# SDCard.net
KiCad netlist of a schematic drawn in Altium Designer
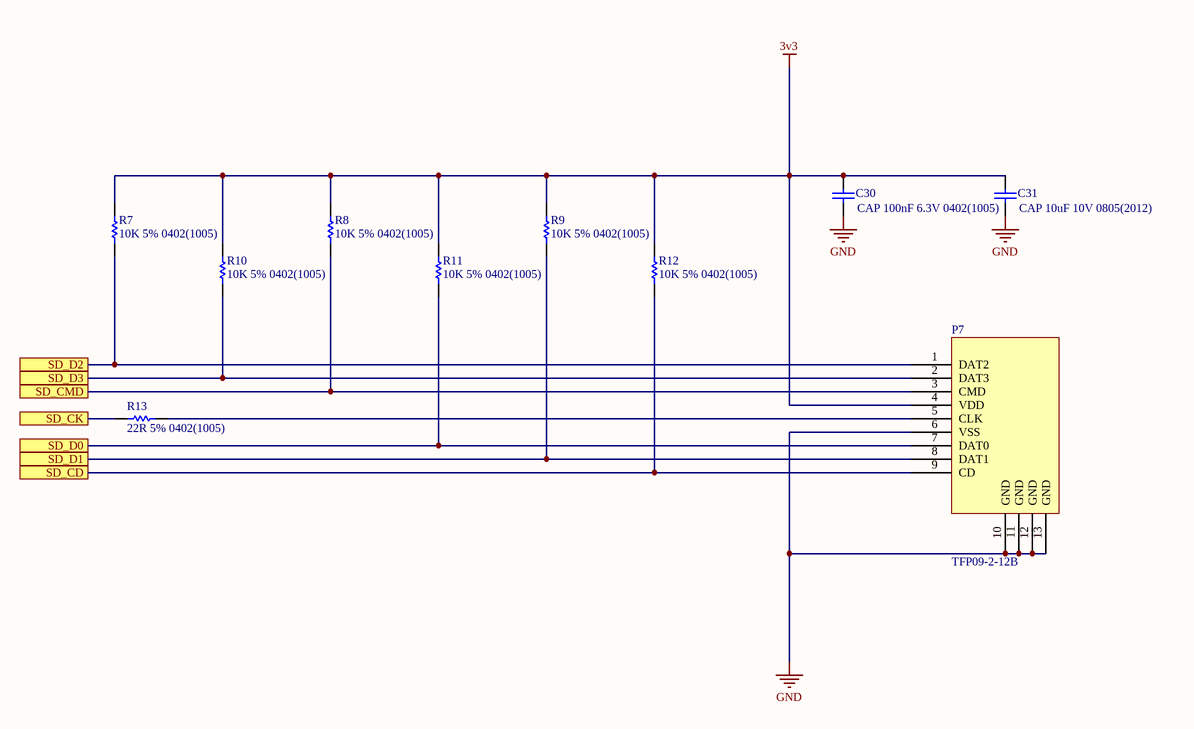
[diagram p0: SDCard.SchDoc]

(export (version "E")
  (design (tool "Eeschema 10.0.6"))
  (components
    (comp (ref "C30")
      (value "CAP 100nF 6.3V 0402(1005)")
      (footprint "CAPC0402(1005)60_M")
      (description "CAP 100nF 6.3V ±20% 0402 (1005 Metric) Thickness 0.6mm SMD")
      (fields (field (name "TOLERANCE") "Â±20%"))
      (libsource (lib "Altium Content Vault") (part "CAP"))
    )
    (comp (ref "C31")
      (value "CAP 10uF 10V 0805(2012)")
      (footprint "CAPC0805(2012)100_N")
      (description "CAP 10uF 10V ±20% 0805 (2012 Metric) Thickness 1mm SMD")
      (fields (field (name "TOLERANCE") "Â±20%"))
      (libsource (lib "Altium Content Vault") (part "CAP"))
    )
    (comp (ref "P7")
      (value "TFP09-2-12B")
      (footprint "TFP09-2-12B")
      (description "MicroSD Card Slot")
      (libsource (lib "Parts") (part "TFP09-2-12B"))
    )
    (comp (ref "R7")
      (value "10K 5% 0402(1005)")
      (footprint "RESC0402(1005)_N")
      (description "10K 0.063W 5% 0402 (1005 Metric)  SMD")
      (fields (field (name "TOLERANCE") "5 %") (field (name "POWER") "0.063 W"))
      (libsource (lib "Altium Content Vault") (part "RES"))
    )
    (comp (ref "R8")
      (value "10K 5% 0402(1005)")
      (footprint "RESC0402(1005)_N")
      (description "10K 0.063W 5% 0402 (1005 Metric)  SMD")
      (fields (field (name "TOLERANCE") "5 %") (field (name "POWER") "0.063 W"))
      (libsource (lib "Altium Content Vault") (part "RES"))
    )
    (comp (ref "R9")
      (value "10K 5% 0402(1005)")
      (footprint "RESC0402(1005)_N")
      (description "10K 0.063W 5% 0402 (1005 Metric)  SMD")
      (fields (field (name "TOLERANCE") "5 %") (field (name "POWER") "0.063 W"))
      (libsource (lib "Altium Content Vault") (part "RES"))
    )
    (comp (ref "R10")
      (value "10K 5% 0402(1005)")
      (footprint "RESC0402(1005)_N")
      (description "10K 0.063W 5% 0402 (1005 Metric)  SMD")
      (fields (field (name "TOLERANCE") "5 %") (field (name "POWER") "0.063 W"))
      (libsource (lib "Altium Content Vault") (part "RES"))
    )
    (comp (ref "R11")
      (value "10K 5% 0402(1005)")
      (footprint "RESC0402(1005)_N")
      (description "10K 0.063W 5% 0402 (1005 Metric)  SMD")
      (fields (field (name "TOLERANCE") "5 %") (field (name "POWER") "0.063 W"))
      (libsource (lib "Altium Content Vault") (part "RES"))
    )
    (comp (ref "R12")
      (value "10K 5% 0402(1005)")
      (footprint "RESC0402(1005)_N")
      (description "10K 0.063W 5% 0402 (1005 Metric)  SMD")
      (fields (field (name "TOLERANCE") "5 %") (field (name "POWER") "0.063 W"))
      (libsource (lib "Altium Content Vault") (part "RES"))
    )
    (comp (ref "R13")
      (value "22R 5% 0402(1005)")
      (footprint "RESC0402(1005)_M")
      (description "22R 0.063W 5% 0402 (1005 Metric)  SMD")
      (fields (field (name "POWER") "0.063 W") (field (name "TOLERANCE") "5 %"))
      (libsource (lib "Altium Content Vault") (part "RES"))
    )
  )
  (nets
    (net (code "1") (name "/SD_CD") (class "Default")
      (node (ref "P7") (pin "9") (pinfunction "CD_9") (pintype "passive"))
      (node (ref "R12") (pin "1") (pinfunction "1_1") (pintype "passive"))
    )
    (net (code "2") (name "/SD_CK") (class "Default")
      (node (ref "R13") (pin "1") (pinfunction "1_1") (pintype "passive"))
    )
    (net (code "3") (name "/SD_CMD") (class "Default")
      (node (ref "P7") (pin "3") (pinfunction "CMD_3") (pintype "passive"))
      (node (ref "R8") (pin "1") (pinfunction "1_1") (pintype "passive"))
    )
    (net (code "4") (name "/SD_D0") (class "Default")
      (node (ref "P7") (pin "7") (pinfunction "DAT0_7") (pintype "passive"))
      (node (ref "R11") (pin "1") (pinfunction "1_1") (pintype "passive"))
    )
    (net (code "5") (name "/SD_D1") (class "Default")
      (node (ref "P7") (pin "8") (pinfunction "DAT1_8") (pintype "passive"))
      (node (ref "R9") (pin "1") (pinfunction "1_1") (pintype "passive"))
    )
    (net (code "6") (name "/SD_D2") (class "Default")
      (node (ref "P7") (pin "1") (pinfunction "DAT2_1") (pintype "passive"))
      (node (ref "R7") (pin "1") (pinfunction "1_1") (pintype "passive"))
    )
    (net (code "7") (name "/SD_D3") (class "Default")
      (node (ref "P7") (pin "2") (pinfunction "DAT3_2") (pintype "passive"))
      (node (ref "R10") (pin "1") (pinfunction "1_1") (pintype "passive"))
    )
    (net (code "8") (name "3v3") (class "Default")
      (node (ref "C30") (pin "2") (pinfunction "2_2") (pintype "passive"))
      (node (ref "C31") (pin "2") (pinfunction "2_2") (pintype "passive"))
      (node (ref "P7") (pin "4") (pinfunction "VDD_4") (pintype "passive"))
      (node (ref "R10") (pin "2") (pinfunction "2_2") (pintype "passive"))
      (node (ref "R11") (pin "2") (pinfunction "2_2") (pintype "passive"))
      (node (ref "R12") (pin "2") (pinfunction "2_2") (pintype "passive"))
      (node (ref "R7") (pin "2") (pinfunction "2_2") (pintype "passive"))
      (node (ref "R8") (pin "2") (pinfunction "2_2") (pintype "passive"))
      (node (ref "R9") (pin "2") (pinfunction "2_2") (pintype "passive"))
    )
    (net (code "9") (name "GND") (class "Default")
      (node (ref "C30") (pin "1") (pinfunction "1_1") (pintype "passive"))
      (node (ref "C31") (pin "1") (pinfunction "1_1") (pintype "passive"))
      (node (ref "P7") (pin "10") (pinfunction "GND_10") (pintype "passive"))
      (node (ref "P7") (pin "11") (pinfunction "GND_11") (pintype "passive"))
      (node (ref "P7") (pin "12") (pinfunction "GND_12") (pintype "passive"))
      (node (ref "P7") (pin "13") (pinfunction "GND_13") (pintype "passive"))
      (node (ref "P7") (pin "6") (pinfunction "VSS_6") (pintype "passive"))
    )
    (net (code "10") (name "Net-(P7-CLK)") (class "Default")
      (node (ref "P7") (pin "5") (pinfunction "CLK_5") (pintype "passive"))
      (node (ref "R13") (pin "2") (pinfunction "2_2") (pintype "passive"))
    )
  )
)
